# I2C_EXTERNAL.net
KiCad netlist of a schematic drawn in Altium Designer
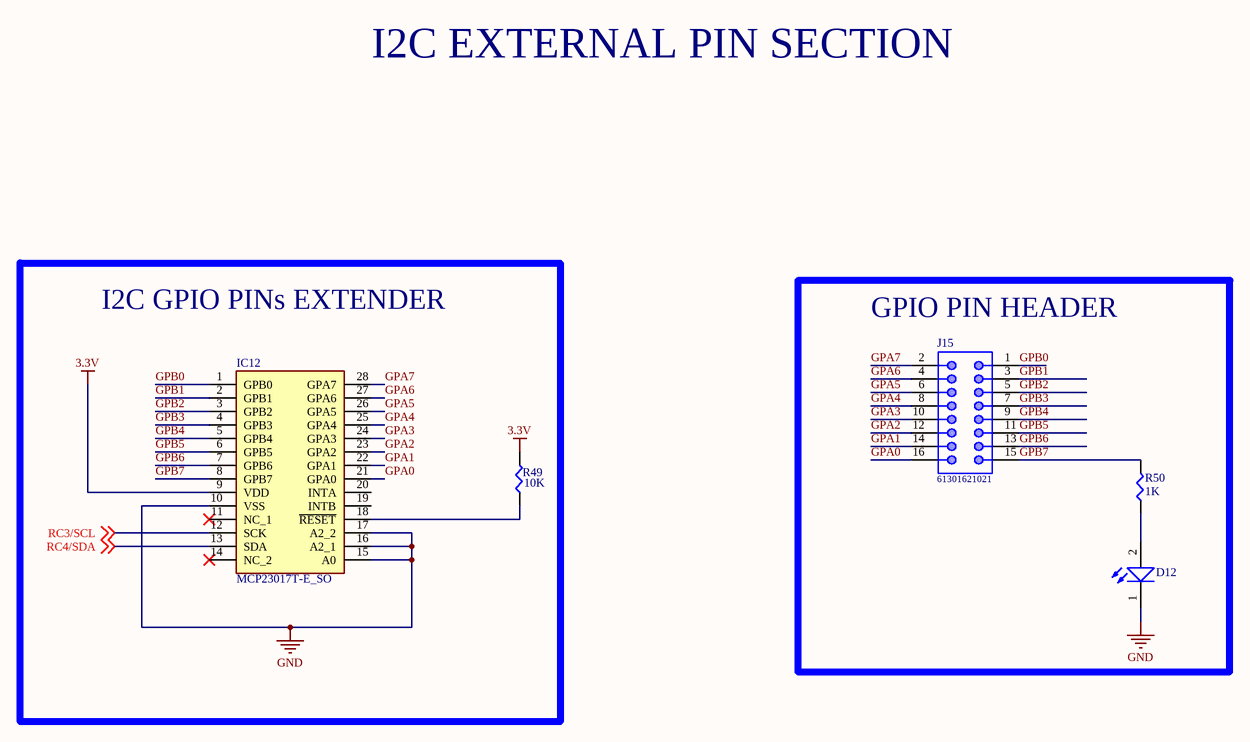
[diagram p0: I2C EXTERNAL.SchDoc]

(export (version "E")
  (design (tool "Eeschema 10.0.6"))
  (components
    (comp (ref "D12")
      (value "150080BS75000")
      (footprint "WL-SMCW_0805")
      (description "WL-SMCW SMD Mono-color Chip LED Waterclear, size 0805, Blue")
      (fields (field (name "PUBLISHER") "Wurth Elektronik"))
      (libsource (lib "SMD LED 0603 t0 1206 WL-SMCW-SMT-LED") (part "150080BS75000"))
    )
    (comp (ref "IC12")
      (value "MCP23017T-E_SO")
      (footprint "SamacSys:SOIC127P1030X265-28N")
      (description "Integrated Circuit")
      (fields
        (field (name "MANUFACTURER_PART_NUMBER") "MCP23017T-E/SO")
        (field (name "MOUSER PART NUMBER") "579-MCP23017T-E/SO")
      )
      (libsource (lib "SamacSys") (part "MCP23017T-E_SO"))
    )
    (comp (ref "J15")
      (value "61301621021")
      (footprint "61301621021")
      (description "WR-PHD Pin Header, THT, pitch 2.54mm, Dual Row, Angled, 16pin")
      (fields (field (name "PUBLISHER") "Wurth Elektronik"))
      (libsource (lib "SIL_Connectors WR-PHD_rev19a") (part "61301621021"))
    )
    (comp (ref "R49")
      (value "10K")
      (footprint "SMD-0805-RES")
      (description "RES SMD 1K OHM 1% 1/8W 0805")
      (fields
        (field (name "PART NUMBER") "ERJ-6ENF1001V")
        (field (name "DIGI-KEY PART NUMBER") "P1.00KCCT-ND")
      )
      (libsource (lib "Panasonic_ERJ_0805") (part "ERJ-6ENF1001V"))
    )
    (comp (ref "R50")
      (value "1K")
      (footprint "SMD-0805-RES")
      (description "RES SMD 1K OHM 1% 1/8W 0805")
      (fields
        (field (name "PART NUMBER") "ERJ-6ENF1001V")
        (field (name "DIGI-KEY PART NUMBER") "P1.00KCCT-ND")
      )
      (libsource (lib "Panasonic_ERJ_0805") (part "ERJ-6ENF1001V"))
    )
  )
  (nets
    (net (code "1") (name "/GPA0") (class "Default")
      (node (ref "IC12") (pin "21") (pinfunction "GPA0_21") (pintype "passive"))
      (node (ref "J15") (pin "16") (pinfunction "16_16") (pintype "passive"))
    )
    (net (code "2") (name "/GPA1") (class "Default")
      (node (ref "IC12") (pin "22") (pinfunction "GPA1_22") (pintype "passive"))
      (node (ref "J15") (pin "14") (pinfunction "14_14") (pintype "passive"))
    )
    (net (code "3") (name "/GPA2") (class "Default")
      (node (ref "IC12") (pin "23") (pinfunction "GPA2_23") (pintype "passive"))
      (node (ref "J15") (pin "12") (pinfunction "12_12") (pintype "passive"))
    )
    (net (code "4") (name "/GPA3") (class "Default")
      (node (ref "IC12") (pin "24") (pinfunction "GPA3_24") (pintype "passive"))
      (node (ref "J15") (pin "10") (pinfunction "10_10") (pintype "passive"))
    )
    (net (code "5") (name "/GPA4") (class "Default")
      (node (ref "IC12") (pin "25") (pinfunction "GPA4_25") (pintype "passive"))
      (node (ref "J15") (pin "8") (pinfunction "8_8") (pintype "passive"))
    )
    (net (code "6") (name "/GPA5") (class "Default")
      (node (ref "IC12") (pin "26") (pinfunction "GPA5_26") (pintype "passive"))
      (node (ref "J15") (pin "6") (pinfunction "6_6") (pintype "passive"))
    )
    (net (code "7") (name "/GPA6") (class "Default")
      (node (ref "IC12") (pin "27") (pinfunction "GPA6_27") (pintype "passive"))
      (node (ref "J15") (pin "4") (pinfunction "4_4") (pintype "passive"))
    )
    (net (code "8") (name "/GPA7") (class "Default")
      (node (ref "IC12") (pin "28") (pinfunction "GPA7_28") (pintype "passive"))
      (node (ref "J15") (pin "2") (pinfunction "2_2") (pintype "passive"))
    )
    (net (code "9") (name "/GPB0") (class "Default")
      (node (ref "IC12") (pin "1") (pinfunction "GPB0_1") (pintype "passive"))
      (node (ref "J15") (pin "1") (pinfunction "1_1") (pintype "passive"))
    )
    (net (code "10") (name "/GPB1") (class "Default")
      (node (ref "IC12") (pin "2") (pinfunction "GPB1_2") (pintype "passive"))
      (node (ref "J15") (pin "3") (pinfunction "3_3") (pintype "passive"))
    )
    (net (code "11") (name "/GPB2") (class "Default")
      (node (ref "IC12") (pin "3") (pinfunction "GPB2_3") (pintype "passive"))
      (node (ref "J15") (pin "5") (pinfunction "5_5") (pintype "passive"))
    )
    (net (code "12") (name "/GPB3") (class "Default")
      (node (ref "IC12") (pin "4") (pinfunction "GPB3_4") (pintype "passive"))
      (node (ref "J15") (pin "7") (pinfunction "7_7") (pintype "passive"))
    )
    (net (code "13") (name "/GPB4") (class "Default")
      (node (ref "IC12") (pin "5") (pinfunction "GPB4_5") (pintype "passive"))
      (node (ref "J15") (pin "9") (pinfunction "9_9") (pintype "passive"))
    )
    (net (code "14") (name "/GPB5") (class "Default")
      (node (ref "IC12") (pin "6") (pinfunction "GPB5_6") (pintype "passive"))
      (node (ref "J15") (pin "11") (pinfunction "11_11") (pintype "passive"))
    )
    (net (code "15") (name "/GPB6") (class "Default")
      (node (ref "IC12") (pin "7") (pinfunction "GPB6_7") (pintype "passive"))
      (node (ref "J15") (pin "13") (pinfunction "13_13") (pintype "passive"))
    )
    (net (code "16") (name "/GPB7") (class "Default")
      (node (ref "IC12") (pin "8") (pinfunction "GPB7_8") (pintype "passive"))
      (node (ref "J15") (pin "15") (pinfunction "15_15") (pintype "passive"))
      (node (ref "R50") (pin "2") (pinfunction "2_2") (pintype "passive"))
    )
    (net (code "17") (name "3.3V") (class "Default")
      (node (ref "IC12") (pin "9") (pinfunction "VDD_9") (pintype "passive"))
      (node (ref "R49") (pin "2") (pinfunction "2_2") (pintype "passive"))
    )
    (net (code "18") (name "GND") (class "Default")
      (node (ref "D12") (pin "1") (pinfunction "K_1") (pintype "passive"))
      (node (ref "IC12") (pin "10") (pinfunction "VSS_10") (pintype "passive"))
      (node (ref "IC12") (pin "15") (pinfunction "A0_15") (pintype "passive"))
      (node (ref "IC12") (pin "16") (pinfunction "A2_1_16") (pintype "passive"))
      (node (ref "IC12") (pin "17") (pinfunction "A2_2_17") (pintype "passive"))
    )
    (net (code "19") (name "Net-(D12-A)") (class "Default")
      (node (ref "D12") (pin "2") (pinfunction "A_2") (pintype "passive"))
      (node (ref "R50") (pin "1") (pinfunction "1_1") (pintype "passive"))
    )
    (net (code "20") (name "Net-(IC12-~{RESET})") (class "Default")
      (node (ref "IC12") (pin "18") (pinfunction "~{RESET}_18") (pintype "passive"))
      (node (ref "R49") (pin "1") (pinfunction "1_1") (pintype "passive"))
    )
    (net (code "21") (name "RC3{slash}SCL") (class "Default")
      (node (ref "IC12") (pin "12") (pinfunction "SCK_12") (pintype "passive"))
    )
    (net (code "22") (name "RC4{slash}SDA") (class "Default")
      (node (ref "IC12") (pin "13") (pinfunction "SDA_13") (pintype "passive"))
    )
    (net (code "23") (name "unconnected-(IC12-INTA-Pad20)") (class "Default")
      (node (ref "IC12") (pin "20") (pinfunction "INTA_20") (pintype "passive"))
    )
    (net (code "24") (name "unconnected-(IC12-INTB-Pad19)") (class "Default")
      (node (ref "IC12") (pin "19") (pinfunction "INTB_19") (pintype "passive"))
    )
    (net (code "25") (name "unconnected-(IC12-NC_1-Pad11)") (class "Default")
      (node (ref "IC12") (pin "11") (pinfunction "NC_1_11") (pintype "passive+no_connect"))
    )
    (net (code "26") (name "unconnected-(IC12-NC_2-Pad14)") (class "Default")
      (node (ref "IC12") (pin "14") (pinfunction "NC_2_14") (pintype "passive+no_connect"))
    )
  )
)
